# chessClock.net
KiCad netlist of a schematic drawn in EAGLE
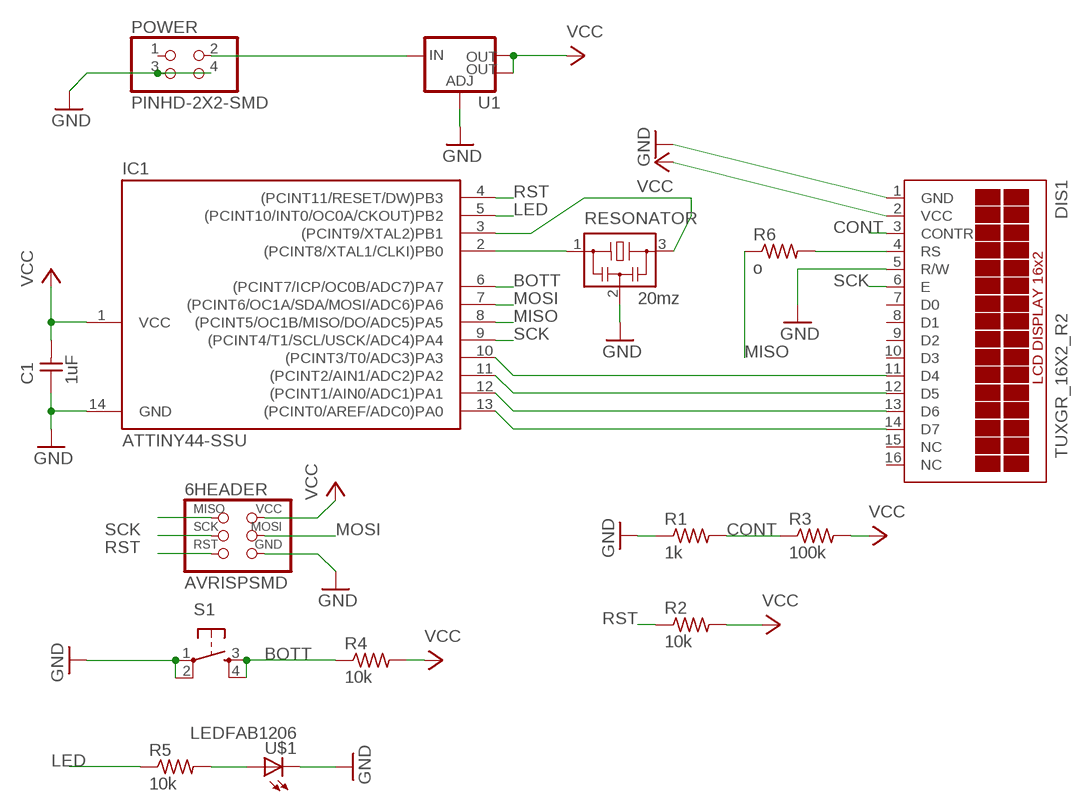
[diagram p0: schematic, sheet 1]

(export (version "E")
  (design (tool "Eeschema 10.0.6"))
  (components
    (comp (ref "6HEADER")
      (value "AVRISPSMD")
      (footprint "eagle-import:2X03SMD")
      (libsource (lib "eagle-import") (part "AVRISPSMD"))
    )
    (comp (ref "C1")
      (value "1uF")
      (footprint "eagle-import:C1206FAB")
      (libsource (lib "eagle-import") (part "CAP-UNPOLARIZEDFAB"))
    )
    (comp (ref "DIS1")
      (value "TUXGR_16X2_R2")
      (footprint "eagle-import:TUXGR_16X2_R2")
      (libsource (lib "eagle-import") (part "TUXGR_16X2_R2"))
    )
    (comp (ref "IC1")
      (value "ATTINY44-SSU")
      (footprint "eagle-import:SOIC14")
      (libsource (lib "eagle-import") (part "ATTINY44-SSU"))
    )
    (comp (ref "POWER")
      (value "PINHD-2X2-SMD")
      (footprint "eagle-import:2X02SMD")
      (libsource (lib "eagle-import") (part "PINHD-2X2-SMD"))
    )
    (comp (ref "R1")
      (value "1k")
      (footprint "eagle-import:R1206FAB")
      (libsource (lib "eagle-import") (part "RES-US1206FAB"))
    )
    (comp (ref "R2")
      (value "10k")
      (footprint "eagle-import:R1206FAB")
      (libsource (lib "eagle-import") (part "RES-US1206FAB"))
    )
    (comp (ref "R3")
      (value "100k")
      (footprint "eagle-import:R1206FAB")
      (libsource (lib "eagle-import") (part "RES-US1206FAB"))
    )
    (comp (ref "R4")
      (value "10k")
      (footprint "eagle-import:R1206FAB")
      (libsource (lib "eagle-import") (part "RES-US1206FAB"))
    )
    (comp (ref "R5")
      (value "10k")
      (footprint "eagle-import:R1206FAB")
      (libsource (lib "eagle-import") (part "RES-US1206FAB"))
    )
    (comp (ref "R6")
      (value "o")
      (footprint "eagle-import:R1206FAB")
      (libsource (lib "eagle-import") (part "RES-US1206FAB"))
    )
    (comp (ref "RESONATOR")
      (value "20mz")
      (footprint "eagle-import:EFOBM")
      (libsource (lib "eagle-import") (part "RESONATOR"))
    )
    (comp (ref "S1")
      (value "6MM_SWITCH6MM_SWITCH")
      (footprint "eagle-import:6MM_SWITCH")
      (libsource (lib "eagle-import") (part "6MM_SWITCH6MM_SWITCH"))
    )
    (comp (ref "U$1")
      (value "LEDFAB1206")
      (footprint "eagle-import:LED1206FAB")
      (libsource (lib "eagle-import") (part "LEDFAB1206"))
    )
    (comp (ref "U1")
      (value "V_REG_LM1117SOT223")
      (footprint "eagle-import:SOT223")
      (libsource (lib "eagle-import") (part "V_REG_LM1117SOT223"))
    )
  )
  (nets
    (net (code "1") (name "/BOTT") (class "Default")
      (node (ref "IC1") (pin "6") (pinfunction "(PCINT7/ICP/OC0B/ADC7)PA7_6") (pintype "bidirectional"))
      (node (ref "R4") (pin "1") (pinfunction "1_1") (pintype "passive"))
      (node (ref "S1") (pin "3") (pinfunction "S_3") (pintype "passive"))
      (node (ref "S1") (pin "4") (pinfunction "S1_4") (pintype "passive"))
    )
    (net (code "2") (name "/CONT") (class "Default")
      (node (ref "DIS1") (pin "3") (pinfunction "CONTR_3") (pintype "input"))
      (node (ref "R1") (pin "2") (pinfunction "2_2") (pintype "passive"))
      (node (ref "R3") (pin "1") (pinfunction "1_1") (pintype "passive"))
    )
    (net (code "3") (name "/LED") (class "Default")
      (node (ref "IC1") (pin "5") (pinfunction "(PCINT10/INT0/OC0A/CKOUT)PB2_5") (pintype "bidirectional"))
      (node (ref "R5") (pin "1") (pinfunction "1_1") (pintype "passive"))
    )
    (net (code "4") (name "/MISO") (class "Default")
      (node (ref "6HEADER") (pin "1") (pinfunction "MISO_1") (pintype "passive"))
      (node (ref "IC1") (pin "8") (pinfunction "(PCINT5/OC1B/MISO/DO/ADC5)PA5_8") (pintype "bidirectional"))
      (node (ref "R6") (pin "1") (pinfunction "1_1") (pintype "passive"))
    )
    (net (code "5") (name "/MOSI") (class "Default")
      (node (ref "6HEADER") (pin "4") (pinfunction "MOSI_4") (pintype "passive"))
      (node (ref "IC1") (pin "7") (pinfunction "(PCINT6/OC1A/SDA/MOSI/ADC6)PA6_7") (pintype "bidirectional"))
    )
    (net (code "6") (name "/RST") (class "Default")
      (node (ref "6HEADER") (pin "5") (pinfunction "RST_5") (pintype "passive"))
      (node (ref "IC1") (pin "4") (pinfunction "(PCINT11/RESET/DW)PB3_4") (pintype "bidirectional"))
      (node (ref "R2") (pin "1") (pinfunction "1_1") (pintype "passive"))
    )
    (net (code "7") (name "/SCK") (class "Default")
      (node (ref "6HEADER") (pin "3") (pinfunction "SCK_3") (pintype "passive"))
      (node (ref "DIS1") (pin "6") (pinfunction "E_6") (pintype "input"))
      (node (ref "IC1") (pin "9") (pinfunction "(PCINT4/T1/SCL/USCK/ADC4)PA4_9") (pintype "bidirectional"))
    )
    (net (code "8") (name "GND") (class "Default")
      (node (ref "6HEADER") (pin "6") (pinfunction "GND_6") (pintype "passive"))
      (node (ref "C1") (pin "1") (pinfunction "1_1") (pintype "passive"))
      (node (ref "DIS1") (pin "1") (pinfunction "GND_1") (pintype "power_in"))
      (node (ref "DIS1") (pin "5") (pinfunction "R/W_5") (pintype "input"))
      (node (ref "IC1") (pin "14") (pinfunction "GND_14") (pintype "power_in"))
      (node (ref "POWER") (pin "3") (pinfunction "3_3") (pintype "passive"))
      (node (ref "POWER") (pin "4") (pinfunction "4_4") (pintype "passive"))
      (node (ref "R1") (pin "1") (pinfunction "1_1") (pintype "passive"))
      (node (ref "RESONATOR") (pin "2") (pinfunction "2_2") (pintype "passive"))
      (node (ref "S1") (pin "1") (pinfunction "P_1") (pintype "passive"))
      (node (ref "S1") (pin "2") (pinfunction "P1_2") (pintype "passive"))
      (node (ref "U$1") (pin "2") (pinfunction "C_2") (pintype "passive"))
      (node (ref "U1") (pin "1") (pinfunction "ADJ_1") (pintype "input"))
    )
    (net (code "9") (name "Net-(DIS1-D4)") (class "Default")
      (node (ref "DIS1") (pin "11") (pinfunction "D4_11") (pintype "input"))
      (node (ref "IC1") (pin "10") (pinfunction "(PCINT3/T0/ADC3)PA3_10") (pintype "bidirectional"))
    )
    (net (code "10") (name "Net-(DIS1-D5)") (class "Default")
      (node (ref "DIS1") (pin "12") (pinfunction "D5_12") (pintype "input"))
      (node (ref "IC1") (pin "11") (pinfunction "(PCINT2/AIN1/ADC2)PA2_11") (pintype "bidirectional"))
    )
    (net (code "11") (name "Net-(DIS1-D6)") (class "Default")
      (node (ref "DIS1") (pin "13") (pinfunction "D6_13") (pintype "input"))
      (node (ref "IC1") (pin "12") (pinfunction "(PCINT1/AIN0/ADC1)PA1_12") (pintype "bidirectional"))
    )
    (net (code "12") (name "Net-(DIS1-D7)") (class "Default")
      (node (ref "DIS1") (pin "14") (pinfunction "D7_14") (pintype "input"))
      (node (ref "IC1") (pin "13") (pinfunction "(PCINT0/AREF/ADC0)PA0_13") (pintype "bidirectional"))
    )
    (net (code "13") (name "Net-(DIS1-RS)") (class "Default")
      (node (ref "DIS1") (pin "4") (pinfunction "RS_4") (pintype "input"))
      (node (ref "R6") (pin "2") (pinfunction "2_2") (pintype "passive"))
    )
    (net (code "14") (name "Net-(IC1-(PCINT8{slash}XTAL1{slash}CLKI)PB0)") (class "Default")
      (node (ref "IC1") (pin "2") (pinfunction "(PCINT8/XTAL1/CLKI)PB0_2") (pintype "bidirectional"))
      (node (ref "RESONATOR") (pin "1") (pinfunction "1_1") (pintype "passive"))
    )
    (net (code "15") (name "Net-(IC1-(PCINT9{slash}XTAL2)PB1)") (class "Default")
      (node (ref "IC1") (pin "3") (pinfunction "(PCINT9/XTAL2)PB1_3") (pintype "bidirectional"))
      (node (ref "RESONATOR") (pin "3") (pinfunction "3_3") (pintype "passive"))
    )
    (net (code "16") (name "Net-(U$1-A)") (class "Default")
      (node (ref "R5") (pin "2") (pinfunction "2_2") (pintype "passive"))
      (node (ref "U$1") (pin "1") (pinfunction "A_1") (pintype "passive"))
    )
    (net (code "17") (name "Net-(U1-IN)") (class "Default")
      (node (ref "POWER") (pin "2") (pinfunction "2_2") (pintype "passive"))
      (node (ref "U1") (pin "3") (pinfunction "IN_3") (pintype "input"))
    )
    (net (code "18") (name "VCC") (class "Default")
      (node (ref "6HEADER") (pin "2") (pinfunction "VCC_2") (pintype "passive"))
      (node (ref "C1") (pin "2") (pinfunction "2_2") (pintype "passive"))
      (node (ref "DIS1") (pin "2") (pinfunction "VCC_2") (pintype "power_in"))
      (node (ref "IC1") (pin "1") (pinfunction "VCC_1") (pintype "power_in"))
      (node (ref "R2") (pin "2") (pinfunction "2_2") (pintype "passive"))
      (node (ref "R3") (pin "2") (pinfunction "2_2") (pintype "passive"))
      (node (ref "R4") (pin "2") (pinfunction "2_2") (pintype "passive"))
      (node (ref "U1") (pin "2") (pinfunction "OUT_2") (pintype "output"))
      (node (ref "U1") (pin "4") (pinfunction "OUT_4") (pintype "output"))
    )
    (net (code "19") (name "unconnected-(DIS1-D0-Pad7)") (class "Default")
      (node (ref "DIS1") (pin "7") (pinfunction "D0_7") (pintype "input"))
    )
    (net (code "20") (name "unconnected-(DIS1-D1-Pad8)") (class "Default")
      (node (ref "DIS1") (pin "8") (pinfunction "D1_8") (pintype "input"))
    )
    (net (code "21") (name "unconnected-(DIS1-D2-Pad9)") (class "Default")
      (node (ref "DIS1") (pin "9") (pinfunction "D2_9") (pintype "input"))
    )
    (net (code "22") (name "unconnected-(DIS1-D3-Pad10)") (class "Default")
      (node (ref "DIS1") (pin "10") (pinfunction "D3_10") (pintype "input"))
    )
    (net (code "23") (name "unconnected-(DIS1-NC-Pad15)") (class "Default")
      (node (ref "DIS1") (pin "15") (pinfunction "NC_15") (pintype "no_connect"))
    )
    (net (code "24") (name "unconnected-(DIS1-NC-Pad16)") (class "Default")
      (node (ref "DIS1") (pin "16") (pinfunction "NC_16") (pintype "no_connect"))
    )
    (net (code "25") (name "unconnected-(POWER-Pad1)") (class "Default")
      (node (ref "POWER") (pin "1") (pinfunction "1_1") (pintype "passive"))
    )
  )
)
